# hc-vitaminder.net
KiCad netlist of a schematic drawn in EAGLE
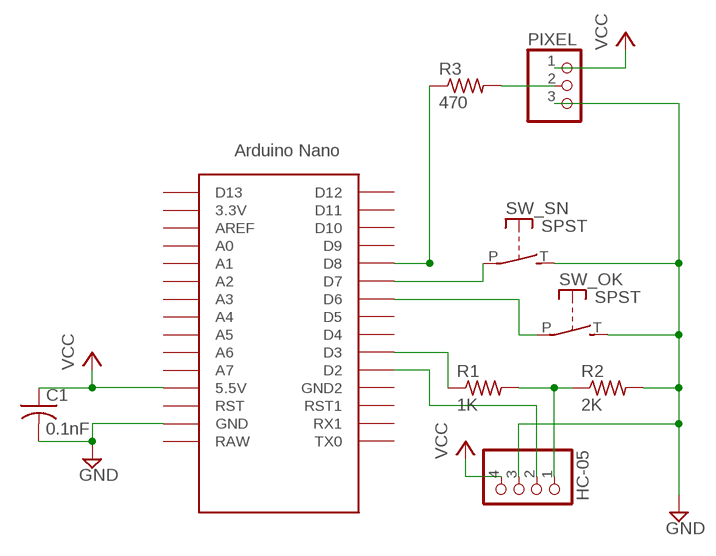
[diagram p0: schematic, sheet 1]

(export (version "E")
  (design (tool "Eeschema 10.0.6"))
  (components
    (comp (ref "C1")
      (value "0.1nF")
      (footprint "eagle-import:C025-024X044")
      (libsource (lib "eagle-import") (part "C-US025-024X044"))
    )
    (comp (ref "HC-05")
      (value "PINHD-1X4")
      (footprint "eagle-import:1X04")
      (libsource (lib "eagle-import") (part "PINHD-1X4"))
    )
    (comp (ref "PIXEL")
      (value "PINHD-1X3")
      (footprint "eagle-import:1X03")
      (libsource (lib "eagle-import") (part "PINHD-1X3"))
    )
    (comp (ref "R1")
      (value "1K")
      (footprint "eagle-import:0309_12")
      (libsource (lib "eagle-import") (part "R-US_0309/12"))
    )
    (comp (ref "R2")
      (value "2K")
      (footprint "eagle-import:0309_12")
      (libsource (lib "eagle-import") (part "R-US_0309/12"))
    )
    (comp (ref "R3")
      (value "470")
      (footprint "eagle-import:0309_12")
      (libsource (lib "eagle-import") (part "R-US_0309/12"))
    )
    (comp (ref "SW_OK")
      (value "SPST")
      (footprint "eagle-import:JUDCOSPST")
      (libsource (lib "eagle-import") (part "SPST"))
    )
    (comp (ref "SW_SN")
      (value "SPST")
      (footprint "eagle-import:JUDCOSPST")
      (libsource (lib "eagle-import") (part "SPST"))
    )
    (comp (ref "U$1")
      (value "NANO")
      (footprint "eagle-import:NANO")
      (libsource (lib "eagle-import") (part "NANO"))
    )
  )
  (nets
    (net (code "1") (name "GND") (class "Default")
      (node (ref "C1") (pin "2") (pinfunction "2_2") (pintype "passive"))
      (node (ref "HC-05") (pin "3") (pinfunction "3_3") (pintype "passive"))
      (node (ref "PIXEL") (pin "3") (pinfunction "3_3") (pintype "passive"))
      (node (ref "R2") (pin "2") (pinfunction "2_2") (pintype "passive"))
      (node (ref "SW_OK") (pin "T") (pinfunction "S_T") (pintype "passive"))
      (node (ref "SW_SN") (pin "T") (pinfunction "S_T") (pintype "passive"))
      (node (ref "U$1") (pin "GND") (pinfunction "GND_GND") (pintype "bidirectional"))
    )
    (net (code "2") (name "Net-(HC-05-Pad1)") (class "Default")
      (node (ref "HC-05") (pin "1") (pinfunction "1_1") (pintype "passive"))
      (node (ref "R1") (pin "2") (pinfunction "2_2") (pintype "passive"))
      (node (ref "R2") (pin "1") (pinfunction "1_1") (pintype "passive"))
    )
    (net (code "3") (name "Net-(HC-05-Pad2)") (class "Default")
      (node (ref "HC-05") (pin "2") (pinfunction "2_2") (pintype "passive"))
      (node (ref "U$1") (pin "D2") (pinfunction "D2_D2") (pintype "bidirectional"))
    )
    (net (code "4") (name "Net-(PIXEL-Pad2)") (class "Default")
      (node (ref "PIXEL") (pin "2") (pinfunction "2_2") (pintype "passive"))
      (node (ref "R3") (pin "2") (pinfunction "2_2") (pintype "passive"))
    )
    (net (code "5") (name "Net-(R1-Pad1)") (class "Default")
      (node (ref "R1") (pin "1") (pinfunction "1_1") (pintype "passive"))
      (node (ref "U$1") (pin "D3") (pinfunction "D3_D3") (pintype "bidirectional"))
    )
    (net (code "6") (name "Net-(R3-Pad1)") (class "Default")
      (node (ref "R3") (pin "1") (pinfunction "1_1") (pintype "passive"))
      (node (ref "U$1") (pin "D8") (pinfunction "D8_D8") (pintype "bidirectional"))
    )
    (net (code "7") (name "Net-(SW_OK-PadP)") (class "Default")
      (node (ref "SW_OK") (pin "P") (pinfunction "P_P") (pintype "passive"))
      (node (ref "U$1") (pin "D6") (pinfunction "D6_D6") (pintype "bidirectional"))
    )
    (net (code "8") (name "Net-(SW_SN-PadP)") (class "Default")
      (node (ref "SW_SN") (pin "P") (pinfunction "P_P") (pintype "passive"))
      (node (ref "U$1") (pin "D7") (pinfunction "D7_D7") (pintype "bidirectional"))
    )
    (net (code "9") (name "VCC") (class "Default")
      (node (ref "C1") (pin "1") (pinfunction "1_1") (pintype "passive"))
      (node (ref "HC-05") (pin "4") (pinfunction "4_4") (pintype "passive"))
      (node (ref "PIXEL") (pin "1") (pinfunction "1_1") (pintype "passive"))
      (node (ref "U$1") (pin "5V") (pinfunction "5.5V_5V") (pintype "bidirectional"))
    )
    (net (code "10") (name "unconnected-(U$1-GND2-PadGND1)") (class "Default")
      (node (ref "U$1") (pin "GND1") (pinfunction "GND2_GND1") (pintype "bidirectional"))
    )
    (net (code "11") (name "unconnected-(U$1-Pad3.3V)") (class "Default")
      (node (ref "U$1") (pin "3.3V") (pinfunction "3.3V_3.3V") (pintype "bidirectional"))
    )
    (net (code "12") (name "unconnected-(U$1-PadA0)") (class "Default")
      (node (ref "U$1") (pin "A0") (pinfunction "A0_A0") (pintype "bidirectional"))
    )
    (net (code "13") (name "unconnected-(U$1-PadA1)") (class "Default")
      (node (ref "U$1") (pin "A1") (pinfunction "A1_A1") (pintype "bidirectional"))
    )
    (net (code "14") (name "unconnected-(U$1-PadA2)") (class "Default")
      (node (ref "U$1") (pin "A2") (pinfunction "A2_A2") (pintype "bidirectional"))
    )
    (net (code "15") (name "unconnected-(U$1-PadA3)") (class "Default")
      (node (ref "U$1") (pin "A3") (pinfunction "A3_A3") (pintype "bidirectional"))
    )
    (net (code "16") (name "unconnected-(U$1-PadA4)") (class "Default")
      (node (ref "U$1") (pin "A4") (pinfunction "A4_A4") (pintype "bidirectional"))
    )
    (net (code "17") (name "unconnected-(U$1-PadA5)") (class "Default")
      (node (ref "U$1") (pin "A5") (pinfunction "A5_A5") (pintype "bidirectional"))
    )
    (net (code "18") (name "unconnected-(U$1-PadA6)") (class "Default")
      (node (ref "U$1") (pin "A6") (pinfunction "A6_A6") (pintype "bidirectional"))
    )
    (net (code "19") (name "unconnected-(U$1-PadA7)") (class "Default")
      (node (ref "U$1") (pin "A7") (pinfunction "A7_A7") (pintype "bidirectional"))
    )
    (net (code "20") (name "unconnected-(U$1-PadAREF)") (class "Default")
      (node (ref "U$1") (pin "AREF") (pinfunction "AREF_AREF") (pintype "bidirectional"))
    )
    (net (code "21") (name "unconnected-(U$1-PadD4)") (class "Default")
      (node (ref "U$1") (pin "D4") (pinfunction "D4_D4") (pintype "bidirectional"))
    )
    (net (code "22") (name "unconnected-(U$1-PadD5)") (class "Default")
      (node (ref "U$1") (pin "D5") (pinfunction "D5_D5") (pintype "bidirectional"))
    )
    (net (code "23") (name "unconnected-(U$1-PadD9)") (class "Default")
      (node (ref "U$1") (pin "D9") (pinfunction "D9_D9") (pintype "bidirectional"))
    )
    (net (code "24") (name "unconnected-(U$1-PadD10)") (class "Default")
      (node (ref "U$1") (pin "D10") (pinfunction "D10_D10") (pintype "bidirectional"))
    )
    (net (code "25") (name "unconnected-(U$1-PadD11)") (class "Default")
      (node (ref "U$1") (pin "D11") (pinfunction "D11_D11") (pintype "bidirectional"))
    )
    (net (code "26") (name "unconnected-(U$1-PadD12)") (class "Default")
      (node (ref "U$1") (pin "D12") (pinfunction "D12_D12") (pintype "bidirectional"))
    )
    (net (code "27") (name "unconnected-(U$1-PadD13)") (class "Default")
      (node (ref "U$1") (pin "D13") (pinfunction "D13_D13") (pintype "bidirectional"))
    )
    (net (code "28") (name "unconnected-(U$1-PadICSP1)") (class "Default")
      (node (ref "U$1") (pin "ICSP1") (pinfunction "ICSP1_ICSP1") (pintype "bidirectional"))
    )
    (net (code "29") (name "unconnected-(U$1-PadICSP2)") (class "Default")
      (node (ref "U$1") (pin "ICSP2") (pinfunction "ICSP2_ICSP2") (pintype "bidirectional"))
    )
    (net (code "30") (name "unconnected-(U$1-PadICSP3)") (class "Default")
      (node (ref "U$1") (pin "ICSP3") (pinfunction "ICSP3_ICSP3") (pintype "bidirectional"))
    )
    (net (code "31") (name "unconnected-(U$1-PadICSP4)") (class "Default")
      (node (ref "U$1") (pin "ICSP4") (pinfunction "ICSP4_ICSP4") (pintype "bidirectional"))
    )
    (net (code "32") (name "unconnected-(U$1-PadICSP5)") (class "Default")
      (node (ref "U$1") (pin "ICSP5") (pinfunction "ICSP5_ICSP5") (pintype "bidirectional"))
    )
    (net (code "33") (name "unconnected-(U$1-PadICSP6)") (class "Default")
      (node (ref "U$1") (pin "ICSP6") (pinfunction "ICSP6_ICSP6") (pintype "bidirectional"))
    )
    (net (code "34") (name "unconnected-(U$1-PadRAW)") (class "Default")
      (node (ref "U$1") (pin "RAW") (pinfunction "RAW_RAW") (pintype "bidirectional"))
    )
    (net (code "35") (name "unconnected-(U$1-PadRST)") (class "Default")
      (node (ref "U$1") (pin "RST") (pinfunction "RST_RST") (pintype "bidirectional"))
    )
    (net (code "36") (name "unconnected-(U$1-PadRST1)") (class "Default")
      (node (ref "U$1") (pin "RST1") (pinfunction "RST1_RST1") (pintype "bidirectional"))
    )
    (net (code "37") (name "unconnected-(U$1-PadRX1)") (class "Default")
      (node (ref "U$1") (pin "RX1") (pinfunction "RX1_RX1") (pintype "bidirectional"))
    )
    (net (code "38") (name "unconnected-(U$1-PadTX0)") (class "Default")
      (node (ref "U$1") (pin "TX0") (pinfunction "TX0_TX0") (pintype "bidirectional"))
    )
  )
)
